# Schematics-2.net
KiCad netlist of a schematic drawn in EAGLE
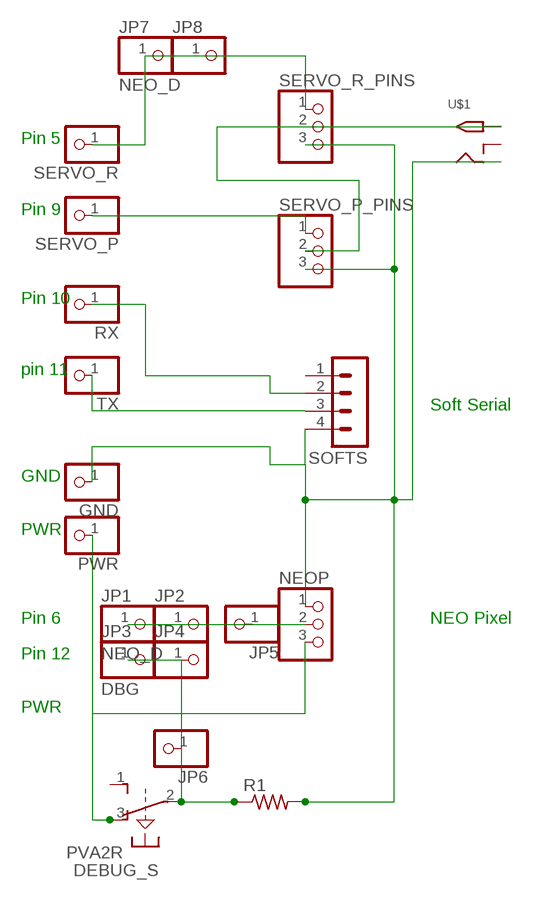
[diagram p0: schematic, sheet 1]

(export (version "E")
  (design (tool "Eeschema 10.0.6"))
  (components
    (comp (ref "DEBUG_S")
      (value "PVA2R")
      (footprint "eagle-import:PVA2R")
      (libsource (lib "eagle-import") (part "PVA2R"))
    )
    (comp (ref "GND")
      (value "PINHD-1X1CB")
      (footprint "eagle-import:1X01-CLEANBIG")
      (libsource (lib "eagle-import") (part "PINHD-1X1CB"))
    )
    (comp (ref "JP1")
      (value "NEO_D")
      (footprint "eagle-import:1X01-CLEANBIG")
      (libsource (lib "eagle-import") (part "PINHD-1X1CB"))
    )
    (comp (ref "JP2")
      (value "PINHD-1X1CB")
      (footprint "eagle-import:1X01-CLEANBIG")
      (libsource (lib "eagle-import") (part "PINHD-1X1CB"))
    )
    (comp (ref "JP3")
      (value "DBG")
      (footprint "eagle-import:1X01-CLEANBIG")
      (libsource (lib "eagle-import") (part "PINHD-1X1CB"))
    )
    (comp (ref "JP4")
      (value "PINHD-1X1CB")
      (footprint "eagle-import:1X01-CLEANBIG")
      (libsource (lib "eagle-import") (part "PINHD-1X1CB"))
    )
    (comp (ref "JP5")
      (value "PINHD-1X1CB")
      (footprint "eagle-import:1X01-CLEANBIG")
      (libsource (lib "eagle-import") (part "PINHD-1X1CB"))
    )
    (comp (ref "JP6")
      (value "PINHD-1X1CB")
      (footprint "eagle-import:1X01-CLEANBIG")
      (libsource (lib "eagle-import") (part "PINHD-1X1CB"))
    )
    (comp (ref "JP7")
      (value "NEO_D")
      (footprint "eagle-import:1X01-CLEANBIG")
      (libsource (lib "eagle-import") (part "PINHD-1X1CB"))
    )
    (comp (ref "JP8")
      (value "PINHD-1X1CB")
      (footprint "eagle-import:1X01-CLEANBIG")
      (libsource (lib "eagle-import") (part "PINHD-1X1CB"))
    )
    (comp (ref "NEOP")
      (value "PINHD-1X3CB")
      (footprint "eagle-import:1X03-CLEANBIG")
      (libsource (lib "eagle-import") (part "PINHD-1X3CB"))
    )
    (comp (ref "PWR")
      (value "PINHD-1X1CB")
      (footprint "eagle-import:1X01-CLEANBIG")
      (libsource (lib "eagle-import") (part "PINHD-1X1CB"))
    )
    (comp (ref "R1")
      (value "R-US_0204/7")
      (footprint "eagle-import:0204_7")
      (libsource (lib "eagle-import") (part "R-US_0204/7"))
    )
    (comp (ref "RX")
      (value "PINHD-1X1CB")
      (footprint "eagle-import:1X01-CLEANBIG")
      (libsource (lib "eagle-import") (part "PINHD-1X1CB"))
    )
    (comp (ref "SERVO_P")
      (value "PINHD-1X1CB")
      (footprint "eagle-import:1X01-CLEANBIG")
      (libsource (lib "eagle-import") (part "PINHD-1X1CB"))
    )
    (comp (ref "SERVO_P_PINS")
      (value "PINHD-1X3CB")
      (footprint "eagle-import:1X03-CLEANBIG")
      (libsource (lib "eagle-import") (part "PINHD-1X3CB"))
    )
    (comp (ref "SERVO_R")
      (value "PINHD-1X1CB")
      (footprint "eagle-import:1X01-CLEANBIG")
      (libsource (lib "eagle-import") (part "PINHD-1X1CB"))
    )
    (comp (ref "SERVO_R_PINS")
      (value "PINHD-1X3CB")
      (footprint "eagle-import:1X03-CLEANBIG")
      (libsource (lib "eagle-import") (part "PINHD-1X3CB"))
    )
    (comp (ref "SOFTS")
      (value "MA04-1")
      (footprint "eagle-import:MA04-1")
      (libsource (lib "eagle-import") (part "MA04-1"))
    )
    (comp (ref "TX")
      (value "PINHD-1X1CB")
      (footprint "eagle-import:1X01-CLEANBIG")
      (libsource (lib "eagle-import") (part "PINHD-1X1CB"))
    )
    (comp (ref "U$1")
      (value "2.1MMJACKTHM")
      (footprint "eagle-import:PJ-102A")
      (libsource (lib "eagle-import") (part "2.1MMJACKTHM"))
    )
  )
  (nets
    (net (code "1") (name "Net-(DEBUG_SA-O)") (class "Default")
      (node (ref "DEBUG_S") (pin "3") (pinfunction "O_3") (pintype "passive"))
      (node (ref "NEOP") (pin "3") (pinfunction "3_3") (pintype "passive"))
      (node (ref "PWR") (pin "1") (pinfunction "1_1") (pintype "passive"))
    )
    (net (code "2") (name "Net-(DEBUG_SA-P)") (class "Default")
      (node (ref "DEBUG_S") (pin "2") (pinfunction "P_2") (pintype "passive"))
      (node (ref "JP3") (pin "1") (pinfunction "1_1") (pintype "passive"))
      (node (ref "JP4") (pin "1") (pinfunction "1_1") (pintype "passive"))
      (node (ref "JP6") (pin "1") (pinfunction "1_1") (pintype "passive"))
      (node (ref "R1") (pin "1") (pinfunction "1_1") (pintype "passive"))
    )
    (net (code "3") (name "Net-(GND-Pad1)") (class "Default")
      (node (ref "GND") (pin "1") (pinfunction "1_1") (pintype "passive"))
      (node (ref "NEOP") (pin "1") (pinfunction "1_1") (pintype "passive"))
      (node (ref "R1") (pin "2") (pinfunction "2_2") (pintype "passive"))
      (node (ref "SERVO_P_PINS") (pin "3") (pinfunction "3_3") (pintype "passive"))
      (node (ref "SERVO_R_PINS") (pin "3") (pinfunction "3_3") (pintype "passive"))
      (node (ref "SOFTS") (pin "4") (pinfunction "4_4") (pintype "passive"))
      (node (ref "U$1") (pin "RING") (pinfunction "RING_RING") (pintype "bidirectional"))
    )
    (net (code "4") (name "Net-(JP1-Pad1)") (class "Default")
      (node (ref "JP1") (pin "1") (pinfunction "1_1") (pintype "passive"))
      (node (ref "JP2") (pin "1") (pinfunction "1_1") (pintype "passive"))
      (node (ref "JP5") (pin "1") (pinfunction "1_1") (pintype "passive"))
      (node (ref "NEOP") (pin "2") (pinfunction "2_2") (pintype "passive"))
    )
    (net (code "5") (name "Net-(JP7-Pad1)") (class "Default")
      (node (ref "JP7") (pin "1") (pinfunction "1_1") (pintype "passive"))
      (node (ref "JP8") (pin "1") (pinfunction "1_1") (pintype "passive"))
      (node (ref "SERVO_R") (pin "1") (pinfunction "1_1") (pintype "passive"))
      (node (ref "SERVO_R_PINS") (pin "1") (pinfunction "1_1") (pintype "passive"))
    )
    (net (code "6") (name "Net-(RX-Pad1)") (class "Default")
      (node (ref "RX") (pin "1") (pinfunction "1_1") (pintype "passive"))
      (node (ref "SOFTS") (pin "2") (pinfunction "2_2") (pintype "passive"))
    )
    (net (code "7") (name "Net-(SERVO_P-Pad1)") (class "Default")
      (node (ref "SERVO_P") (pin "1") (pinfunction "1_1") (pintype "passive"))
      (node (ref "SERVO_P_PINS") (pin "1") (pinfunction "1_1") (pintype "passive"))
    )
    (net (code "8") (name "Net-(SERVO_P_PINS-Pad2)") (class "Default")
      (node (ref "SERVO_P_PINS") (pin "2") (pinfunction "2_2") (pintype "passive"))
      (node (ref "SERVO_R_PINS") (pin "2") (pinfunction "2_2") (pintype "passive"))
      (node (ref "U$1") (pin "TIP") (pinfunction "TIP_TIP") (pintype "bidirectional"))
    )
    (net (code "9") (name "Net-(SOFTS-Pad3)") (class "Default")
      (node (ref "SOFTS") (pin "3") (pinfunction "3_3") (pintype "passive"))
      (node (ref "TX") (pin "1") (pinfunction "1_1") (pintype "passive"))
    )
    (net (code "10") (name "unconnected-(DEBUG_SA-S-Pad1)") (class "Default")
      (node (ref "DEBUG_S") (pin "1") (pinfunction "S_1") (pintype "passive"))
    )
    (net (code "11") (name "unconnected-(SOFTS-Pad1)") (class "Default")
      (node (ref "SOFTS") (pin "1") (pinfunction "1_1") (pintype "passive"))
    )
    (net (code "12") (name "unconnected-(U$1-PadRING_SW)") (class "Default")
      (node (ref "U$1") (pin "RING_SW") (pinfunction "RING_SW_RING_SW") (pintype "bidirectional"))
    )
  )
)
